# satFloat.net
KiCad netlist of a schematic drawn in Altium Designer
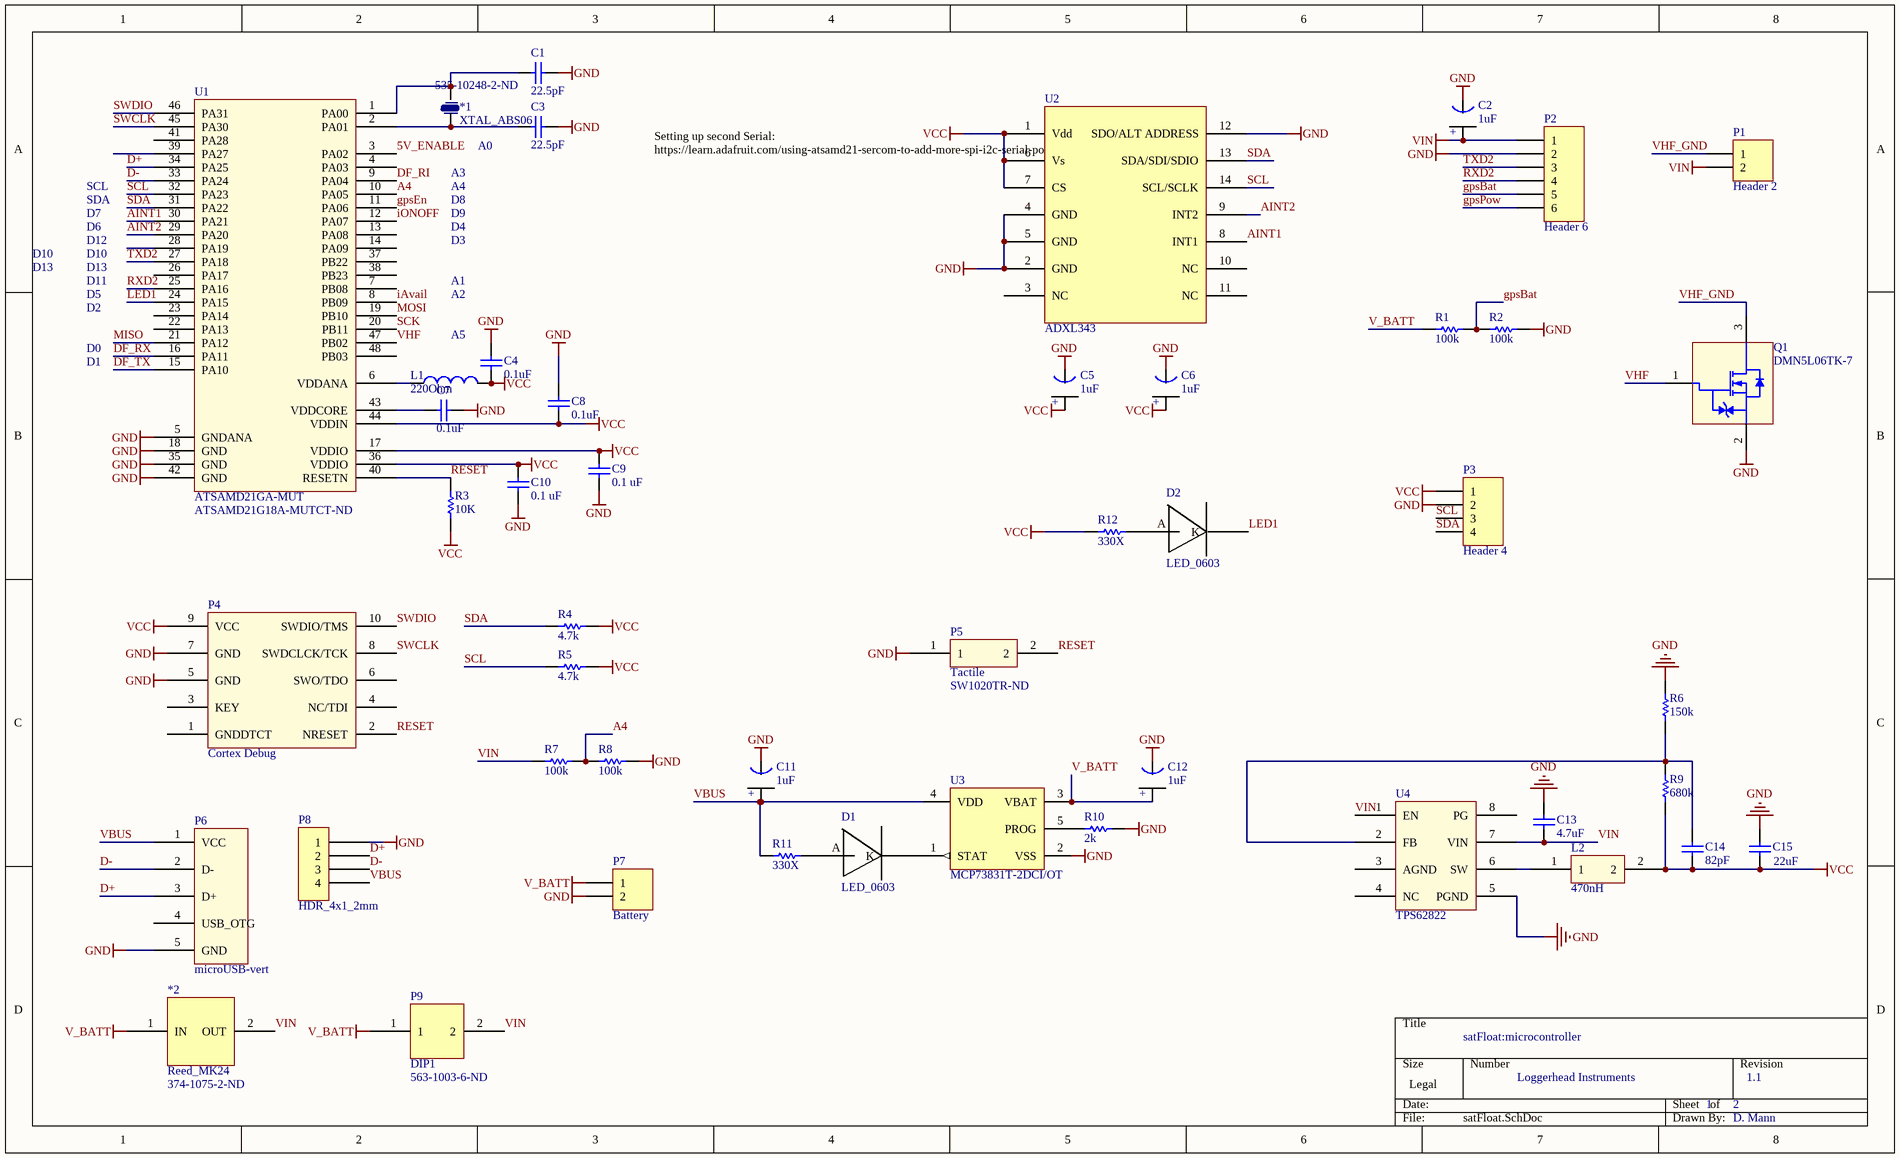
[diagram p0: satFloat.SchDoc]

(export (version "E")
  (design (tool "Eeschema 10.0.6"))
  (components
    (comp (ref "*1")
      (value "XTAL_ABS06")
      (footprint "XTAL-ABS06")
      (fields (field (name "SUPPLIER PART NUMBER 1") "535-10248-2-ND"))
      (libsource (lib "Loggerhead") (part "XTAL_ABS06"))
    )
    (comp (ref "*2")
      (value "Reed_MK24")
      (footprint "Reed MK24-B-3")
      (fields (field (name "SUPPLIER PART NUMBER 1") "374-1075-2-ND"))
      (libsource (lib "Loggerhead") (part "Reed_MK24"))
    )
    (comp (ref "C1")
      (value "22.5pF")
      (footprint "0402")
      (description "Ceramic Chip Capacitor - Standard")
      (fields (field (name "PUBLISHER") "Altium Limited"))
      (libsource (lib "KEMET Chip Capacitor") (part "C0402"))
    )
    (comp (ref "C2") (value "1uF") (footprint "Tant0805") (libsource (lib "Loggerhead") (part "Tant0805")))
    (comp (ref "C3")
      (value "22.5pF")
      (footprint "0402")
      (description "Ceramic Chip Capacitor - Standard")
      (fields (field (name "PUBLISHER") "Altium Limited"))
      (libsource (lib "KEMET Chip Capacitor") (part "C0402"))
    )
    (comp (ref "C4")
      (value "0.1uF")
      (footprint "0402")
      (description "Ceramic Chip Capacitor - Standard")
      (fields (field (name "PUBLISHER") "Altium Limited"))
      (libsource (lib "KEMET Chip Capacitor") (part "C0402"))
    )
    (comp (ref "C5") (value "1uF") (footprint "Tant0805") (libsource (lib "Loggerhead") (part "Tant0805")))
    (comp (ref "C6") (value "1uF") (footprint "Tant0805") (libsource (lib "Loggerhead") (part "Tant0805")))
    (comp (ref "C7")
      (value "0.1uF")
      (footprint "0402")
      (description "Ceramic Chip Capacitor - Standard")
      (fields (field (name "PUBLISHER") "Altium Limited"))
      (libsource (lib "KEMET Chip Capacitor") (part "C0402"))
    )
    (comp (ref "C8")
      (value "0.1uF")
      (footprint "0402")
      (description "Ceramic Chip Capacitor - Standard")
      (fields (field (name "PUBLISHER") "Altium Limited"))
      (libsource (lib "KEMET Chip Capacitor") (part "C0402"))
    )
    (comp (ref "C9")
      (value "0.1 uF")
      (footprint "0402")
      (description "Ceramic Chip Capacitor - Standard")
      (fields (field (name "PUBLISHER") "Altium Limited"))
      (libsource (lib "KEMET Chip Capacitor") (part "C0402"))
    )
    (comp (ref "C10")
      (value "0.1 uF")
      (footprint "0402")
      (description "Ceramic Chip Capacitor - Standard")
      (fields (field (name "PUBLISHER") "Altium Limited"))
      (libsource (lib "KEMET Chip Capacitor") (part "C0402"))
    )
    (comp (ref "C11") (value "1uF") (footprint "Tant0805") (libsource (lib "Loggerhead") (part "Tant0805")))
    (comp (ref "C12") (value "1uF") (footprint "Tant0805") (libsource (lib "Loggerhead") (part "Tant0805")))
    (comp (ref "C13")
      (value "4.7uF")
      (footprint "0603")
      (description "Ceramic Chip Capacitor - Standard")
      (fields (field (name "PUBLISHER") "Altium Limited"))
      (libsource (lib "KEMET Chip Capacitor") (part "C0603"))
    )
    (comp (ref "C14")
      (value "82pF")
      (footprint "0402")
      (description "Ceramic Chip Capacitor - Standard")
      (fields (field (name "PUBLISHER") "Altium Limited"))
      (libsource (lib "KEMET Chip Capacitor") (part "C0402"))
    )
    (comp (ref "C15")
      (value "22uF")
      (footprint "0603")
      (description "Ceramic Chip Capacitor - Standard")
      (fields (field (name "PUBLISHER") "Altium Limited"))
      (libsource (lib "KEMET Chip Capacitor") (part "C0603"))
    )
    (comp (ref "D1")
      (value "LED_0603")
      (footprint "Diode0603")
      (libsource (lib "Loggerhead") (part "LED_0603"))
    )
    (comp (ref "D2")
      (value "LED_0603")
      (footprint "Diode0603")
      (libsource (lib "Loggerhead") (part "LED_0603"))
    )
    (comp (ref "L1")
      (value "220Ohm")
      (footprint "0805 (M2125) Ferrite")
      (description "Ferrite 25mOhm@DC,  60 Ohm@100MHz")
      (fields
        (field (name "CREATOR AND DATE") "Design Engineer's Name")
        (field (name "FOOTPRINT VERIFIED BY") "*")
        (field (name "SCHEMATIC VERIFIED BY") "*")
        (field (name "VENDOR INFO VERIFIED BY") "*")
      )
      (libsource (lib "Flanery") (part "Ferrite 0805(M2125) 3A"))
    )
    (comp (ref "L2")
      (value "470nH")
      (footprint "Inductor_470NH")
      (libsource (lib "Loggerhead") (part "Inductor_470NH"))
    )
    (comp (ref "P1")
      (value "Header 2")
      (footprint "HDR1X2")
      (description "Header, 2-Pin")
      (fields (field (name "PUBLISHER") "Altium Limited"))
      (libsource (lib "Miscellaneous Connectors") (part "Header 2"))
    )
    (comp (ref "P2")
      (value "Header 6")
      (footprint "HDR1X6")
      (description "Header, 6-Pin")
      (fields (field (name "PUBLISHER") "Altium Limited"))
      (libsource (lib "Miscellaneous Connectors") (part "Header 6"))
    )
    (comp (ref "P3")
      (value "Header 4")
      (footprint "HDR1X4")
      (description "Header, 4-Pin")
      (fields (field (name "PUBLISHER") "Altium Limited"))
      (libsource (lib "Miscellaneous Connectors") (part "Header 4"))
    )
    (comp (ref "P4")
      (value "Cortex Debug")
      (footprint "Header_2x5_50mil")
      (libsource (lib "Loggerhead") (part "CortexDebug"))
    )
    (comp (ref "P5")
      (value "Tactile")
      (footprint "Tactile-B3U-1000")
      (fields (field (name "SUPPLIER PART NUMBER 1") "SW1020TR-ND"))
      (libsource (lib "Loggerhead") (part "Tactile_B3U-1000"))
    )
    (comp (ref "P6")
      (value "microUSB-vert")
      (footprint "MICROUSB-VERT")
      (description "Molex 105133-0011")
      (libsource (lib "Loggerhead") (part "microUSB-vert"))
    )
    (comp (ref "P7")
      (value "Battery")
      (footprint "HDR1X2")
      (description "Header, 2-Pin")
      (fields (field (name "PUBLISHER") "Altium Limited"))
      (libsource (lib "Miscellaneous Connectors") (part "Header 2"))
    )
    (comp (ref "P8")
      (value "HDR_4x1_2mm")
      (footprint "Hdr_4x1_2mm")
      (libsource (lib "Loggerhead") (part "HDR_4x1_2mm"))
    )
    (comp (ref "P9")
      (value "DIP1")
      (footprint "DIP1")
      (fields (field (name "SUPPLIER PART NUMBER 1") "563-1003-6-ND"))
      (libsource (lib "Loggerhead") (part "DIP1"))
    )
    (comp (ref "Q1")
      (value "DMN5L06TK-7")
      (footprint "SOT-523")
      (description "Ultra-low leakage Enhanced MOSFET")
      (fields
        (field (name "CREATOR AND DATE") "Will Flanery 2010-09-02")
        (field (name "FOOTPRINT VERIFIED BY") "*")
        (field (name "SCHEMATIC VERIFIED BY") "*")
        (field (name "VENDOR INFO VERIFIED BY") "*")
      )
      (libsource (lib "Flanery") (part "FET DMN5L06TK-7"))
    )
    (comp (ref "R1")
      (value "100k")
      (footprint "3-0603")
      (fields (field (name "PUBLISHER") "Altium Limited"))
      (libsource (lib "Panasonic Resistor") (part "ERJ3RK"))
    )
    (comp (ref "R2")
      (value "100k")
      (footprint "3-0603")
      (fields (field (name "PUBLISHER") "Altium Limited"))
      (libsource (lib "Panasonic Resistor") (part "ERJ3RK"))
    )
    (comp (ref "R3")
      (value "10K")
      (footprint "3-0603")
      (fields (field (name "PUBLISHER") "Altium Limited"))
      (libsource (lib "Panasonic Resistor") (part "ERJ3RK"))
    )
    (comp (ref "R4")
      (value "4.7k")
      (footprint "3-0603")
      (fields (field (name "PUBLISHER") "Altium Limited"))
      (libsource (lib "Panasonic Resistor") (part "ERJ3RK"))
    )
    (comp (ref "R5")
      (value "4.7k")
      (footprint "3-0603")
      (fields (field (name "PUBLISHER") "Altium Limited"))
      (libsource (lib "Panasonic Resistor") (part "ERJ3RK"))
    )
    (comp (ref "R6")
      (value "150k")
      (footprint "3-0603")
      (fields (field (name "PUBLISHER") "Altium Limited"))
      (libsource (lib "Panasonic Resistor") (part "ERJ3RK"))
    )
    (comp (ref "R7")
      (value "100k")
      (footprint "3-0603")
      (fields (field (name "PUBLISHER") "Altium Limited"))
      (libsource (lib "Panasonic Resistor") (part "ERJ3RK"))
    )
    (comp (ref "R8")
      (value "100k")
      (footprint "3-0603")
      (fields (field (name "PUBLISHER") "Altium Limited"))
      (libsource (lib "Panasonic Resistor") (part "ERJ3RK"))
    )
    (comp (ref "R9")
      (value "680k")
      (footprint "3-0603")
      (fields (field (name "PUBLISHER") "Altium Limited"))
      (libsource (lib "Panasonic Resistor") (part "ERJ3RK"))
    )
    (comp (ref "R10")
      (value "2k")
      (footprint "3-0603")
      (fields (field (name "PUBLISHER") "Altium Limited"))
      (libsource (lib "Panasonic Resistor") (part "ERJ3RK"))
    )
    (comp (ref "R11")
      (value "330X")
      (footprint "3-0603")
      (fields (field (name "PUBLISHER") "Altium Limited"))
      (libsource (lib "Panasonic Resistor") (part "ERJ3RK"))
    )
    (comp (ref "R12")
      (value "330X")
      (footprint "3-0603")
      (fields (field (name "PUBLISHER") "Altium Limited"))
      (libsource (lib "Panasonic Resistor") (part "ERJ3RK"))
    )
    (comp (ref "U1")
      (value "ATSAMD21GA-MUT")
      (footprint "QFN127P600-8N")
      (fields (field (name "SUPPLIER PART NUMBER 1") "ATSAMD21G18A-MUTCT-ND"))
      (libsource (lib "Loggerhead") (part "ATSAMD21G18"))
    )
    (comp (ref "U2") (value "ADXL343") (footprint "ADXL345") (libsource (lib "Loggerhead") (part "ADXL345")))
    (comp (ref "U3")
      (value "MCP73831T-2DCI/OT")
      (footprint "SOT-23-OT5_N")
      (libsource (lib "Microchip Power Management Battery Management") (part "MCP73831T-2DCI/OT"))
    )
    (comp (ref "U4")
      (value "TPS62822")
      (footprint "TPS62822_SOP8")
      (description "Step-down converter")
      (libsource (lib "Loggerhead") (part "TPS62822"))
    )
  )
  (nets
    (net (code "1") (name "/5V_ENABLE") (class "Default")
      (node (ref "U1") (pin "3") (pinfunction "PA02_3") (pintype "passive"))
    )
    (net (code "2") (name "/A4") (class "Default")
      (node (ref "R7") (pin "1") (pinfunction "1_1") (pintype "passive"))
      (node (ref "R8") (pin "2") (pinfunction "2_2") (pintype "passive"))
      (node (ref "U1") (pin "10") (pinfunction "PA05_10") (pintype "passive"))
    )
    (net (code "3") (name "/AINT1") (class "Default")
      (node (ref "U1") (pin "30") (pinfunction "PA21_30") (pintype "passive"))
      (node (ref "U2") (pin "8") (pinfunction "INT1_8") (pintype "passive"))
    )
    (net (code "4") (name "/AINT2") (class "Default")
      (node (ref "U1") (pin "29") (pinfunction "PA20_29") (pintype "passive"))
      (node (ref "U2") (pin "9") (pinfunction "INT2_9") (pintype "passive"))
    )
    (net (code "5") (name "/D+") (class "Default")
      (node (ref "P6") (pin "3") (pinfunction "D+_3") (pintype "passive"))
      (node (ref "P8") (pin "2") (pinfunction "2_2") (pintype "passive"))
      (node (ref "U1") (pin "34") (pinfunction "PA25_34") (pintype "passive"))
    )
    (net (code "6") (name "/D-") (class "Default")
      (node (ref "P6") (pin "2") (pinfunction "D-_2") (pintype "passive"))
      (node (ref "P8") (pin "3") (pinfunction "3_3") (pintype "passive"))
      (node (ref "U1") (pin "33") (pinfunction "PA24_33") (pintype "passive"))
    )
    (net (code "7") (name "/DF_RI") (class "Default")
      (node (ref "U1") (pin "9") (pinfunction "PA04_9") (pintype "passive"))
    )
    (net (code "8") (name "/DF_RX") (class "Default")
      (node (ref "U1") (pin "16") (pinfunction "PA11_16") (pintype "passive"))
    )
    (net (code "9") (name "/DF_TX") (class "Default")
      (node (ref "U1") (pin "15") (pinfunction "PA10_15") (pintype "passive"))
    )
    (net (code "10") (name "/LED1") (class "Default")
      (node (ref "D2") (pin "K") (pinfunction "K_K") (pintype "passive"))
      (node (ref "U1") (pin "24") (pinfunction "PA15_24") (pintype "passive"))
    )
    (net (code "11") (name "/MISO") (class "Default")
      (node (ref "U1") (pin "21") (pinfunction "PA12_21") (pintype "passive"))
    )
    (net (code "12") (name "/MOSI") (class "Default")
      (node (ref "U1") (pin "19") (pinfunction "PB10_19") (pintype "passive"))
    )
    (net (code "13") (name "/RESET") (class "Default")
      (node (ref "P4") (pin "2") (pinfunction "NRESET_2") (pintype "passive"))
      (node (ref "P5") (pin "2") (pinfunction "2_2") (pintype "passive"))
      (node (ref "R3") (pin "2") (pinfunction "2_2") (pintype "passive"))
      (node (ref "U1") (pin "40") (pinfunction "RESETN_40") (pintype "passive"))
    )
    (net (code "14") (name "/RXD2") (class "Default")
      (node (ref "P2") (pin "4") (pinfunction "4_4") (pintype "passive"))
      (node (ref "U1") (pin "25") (pinfunction "PA16_25") (pintype "passive"))
    )
    (net (code "15") (name "/SCK") (class "Default")
      (node (ref "U1") (pin "20") (pinfunction "PB11_20") (pintype "passive"))
    )
    (net (code "16") (name "/SCL") (class "Default")
      (node (ref "P3") (pin "3") (pinfunction "3_3") (pintype "passive"))
      (node (ref "R5") (pin "1") (pinfunction "1_1") (pintype "passive"))
      (node (ref "U1") (pin "32") (pinfunction "PA23_32") (pintype "passive"))
      (node (ref "U2") (pin "14") (pinfunction "SCL/SCLK_14") (pintype "passive"))
    )
    (net (code "17") (name "/SDA") (class "Default")
      (node (ref "P3") (pin "4") (pinfunction "4_4") (pintype "passive"))
      (node (ref "R4") (pin "2") (pinfunction "2_2") (pintype "passive"))
      (node (ref "U1") (pin "31") (pinfunction "PA22_31") (pintype "passive"))
      (node (ref "U2") (pin "13") (pinfunction "SDA/SDI/SDIO_13") (pintype "passive"))
    )
    (net (code "18") (name "/SWCLK") (class "Default")
      (node (ref "P4") (pin "8") (pinfunction "SWDCLCK/TCK_8") (pintype "passive"))
      (node (ref "U1") (pin "45") (pinfunction "PA30_45") (pintype "passive"))
    )
    (net (code "19") (name "/SWDIO") (class "Default")
      (node (ref "P4") (pin "10") (pinfunction "SWDIO/TMS_10") (pintype "passive"))
      (node (ref "U1") (pin "46") (pinfunction "PA31_46") (pintype "passive"))
    )
    (net (code "20") (name "/TXD2") (class "Default")
      (node (ref "P2") (pin "3") (pinfunction "3_3") (pintype "passive"))
      (node (ref "U1") (pin "27") (pinfunction "PA18_27") (pintype "passive"))
    )
    (net (code "21") (name "/VBUS") (class "Default")
      (node (ref "C11") (pin "2") (pinfunction "+_2") (pintype "passive"))
      (node (ref "P6") (pin "1") (pinfunction "VCC_1") (pintype "passive"))
      (node (ref "P8") (pin "4") (pinfunction "4_4") (pintype "passive"))
      (node (ref "R11") (pin "1") (pinfunction "1_1") (pintype "passive"))
      (node (ref "U3") (pin "4") (pinfunction "VDD_4") (pintype "power_in"))
    )
    (net (code "22") (name "/VHF") (class "Default")
      (node (ref "Q1") (pin "1") (pinfunction "G_1") (pintype "passive"))
      (node (ref "U1") (pin "47") (pinfunction "PB02_47") (pintype "passive"))
    )
    (net (code "23") (name "/VHF_GND") (class "Default")
      (node (ref "P1") (pin "1") (pinfunction "1_1") (pintype "passive"))
      (node (ref "Q1") (pin "3") (pinfunction "D_3") (pintype "passive"))
    )
    (net (code "24") (name "/gpsBat") (class "Default")
      (node (ref "P2") (pin "5") (pinfunction "5_5") (pintype "passive"))
      (node (ref "R1") (pin "1") (pinfunction "1_1") (pintype "passive"))
      (node (ref "R2") (pin "2") (pinfunction "2_2") (pintype "passive"))
    )
    (net (code "25") (name "/gpsEn") (class "Default")
      (node (ref "U1") (pin "11") (pinfunction "PA06_11") (pintype "passive"))
    )
    (net (code "26") (name "/gpsPow") (class "Default")
      (node (ref "P2") (pin "6") (pinfunction "6_6") (pintype "passive"))
    )
    (net (code "27") (name "/iAvail") (class "Default")
      (node (ref "U1") (pin "8") (pinfunction "PB09_8") (pintype "passive"))
    )
    (net (code "28") (name "/iONOFF") (class "Default")
      (node (ref "U1") (pin "12") (pinfunction "PA07_12") (pintype "passive"))
    )
    (net (code "29") (name "GND") (class "Default")
      (node (ref "C1") (pin "1") (pinfunction "1_1") (pintype "passive"))
      (node (ref "C10") (pin "2") (pinfunction "2_2") (pintype "passive"))
      (node (ref "C11") (pin "1") (pinfunction "GND_1") (pintype "passive"))
      (node (ref "C12") (pin "1") (pinfunction "GND_1") (pintype "passive"))
      (node (ref "C13") (pin "1") (pinfunction "1_1") (pintype "passive"))
      (node (ref "C15") (pin "1") (pinfunction "1_1") (pintype "passive"))
      (node (ref "C2") (pin "1") (pinfunction "GND_1") (pintype "passive"))
      (node (ref "C3") (pin "1") (pinfunction "1_1") (pintype "passive"))
      (node (ref "C4") (pin "2") (pinfunction "2_2") (pintype "passive"))
      (node (ref "C5") (pin "1") (pinfunction "GND_1") (pintype "passive"))
      (node (ref "C6") (pin "1") (pinfunction "GND_1") (pintype "passive"))
      (node (ref "C7") (pin "2") (pinfunction "2_2") (pintype "passive"))
      (node (ref "C8") (pin "2") (pinfunction "2_2") (pintype "passive"))
      (node (ref "C9") (pin "2") (pinfunction "2_2") (pintype "passive"))
      (node (ref "P2") (pin "2") (pinfunction "2_2") (pintype "passive"))
      (node (ref "P3") (pin "2") (pinfunction "2_2") (pintype "passive"))
      (node (ref "P4") (pin "5") (pinfunction "GND_5") (pintype "passive"))
      (node (ref "P4") (pin "7") (pinfunction "GND_7") (pintype "passive"))
      (node (ref "P5") (pin "1") (pinfunction "1_1") (pintype "passive"))
      (node (ref "P6") (pin "5") (pinfunction "GND_5") (pintype "passive"))
      (node (ref "P7") (pin "2") (pinfunction "2_2") (pintype "passive"))
      (node (ref "P8") (pin "1") (pinfunction "1_1") (pintype "passive"))
      (node (ref "Q1") (pin "2") (pinfunction "S_2") (pintype "passive"))
      (node (ref "R10") (pin "1") (pinfunction "1_1") (pintype "passive"))
      (node (ref "R2") (pin "1") (pinfunction "1_1") (pintype "passive"))
      (node (ref "R6") (pin "2") (pinfunction "2_2") (pintype "passive"))
      (node (ref "R8") (pin "1") (pinfunction "1_1") (pintype "passive"))
      (node (ref "U1") (pin "18") (pinfunction "GND_18") (pintype "passive"))
      (node (ref "U1") (pin "35") (pinfunction "GND_35") (pintype "passive"))
      (node (ref "U1") (pin "42") (pinfunction "GND_42") (pintype "passive"))
      (node (ref "U1") (pin "5") (pinfunction "GNDANA_5") (pintype "passive"))
      (node (ref "U2") (pin "12") (pinfunction "SDO/ALT_ADDRESS_12") (pintype "passive"))
      (node (ref "U2") (pin "2") (pinfunction "GND_2") (pintype "passive"))
      (node (ref "U2") (pin "4") (pinfunction "GND_4") (pintype "passive"))
      (node (ref "U2") (pin "5") (pinfunction "GND_5") (pintype "passive"))
      (node (ref "U3") (pin "2") (pinfunction "VSS_2") (pintype "power_in"))
      (node (ref "U4") (pin "5") (pinfunction "PGND_5") (pintype "passive"))
    )
    (net (code "30") (name "Net-(D1-PadA)") (class "Default")
      (node (ref "D1") (pin "A") (pinfunction "A_A") (pintype "passive"))
      (node (ref "R11") (pin "2") (pinfunction "2_2") (pintype "passive"))
    )
    (net (code "31") (name "Net-(D2-PadA)") (class "Default")
      (node (ref "D2") (pin "A") (pinfunction "A_A") (pintype "passive"))
      (node (ref "R12") (pin "2") (pinfunction "2_2") (pintype "passive"))
    )
    (net (code "32") (name "Net-(U1-PA00)") (class "Default")
      (node (ref "*1") (pin "2") (pinfunction "2_2") (pintype "passive"))
      (node (ref "C1") (pin "2") (pinfunction "2_2") (pintype "passive"))
      (node (ref "U1") (pin "1") (pinfunction "PA00_1") (pintype "passive"))
    )
    (net (code "33") (name "Net-(U1-PA01)") (class "Default")
      (node (ref "*1") (pin "1") (pinfunction "1_1") (pintype "passive"))
      (node (ref "C3") (pin "2") (pinfunction "2_2") (pintype "passive"))
      (node (ref "U1") (pin "2") (pinfunction "PA01_2") (pintype "passive"))
    )
    (net (code "34") (name "Net-(U1-VDDANA)") (class "Default")
      (node (ref "L1") (pin "1") (pinfunction "1_1") (pintype "passive"))
      (node (ref "U1") (pin "6") (pinfunction "VDDANA_6") (pintype "passive"))
    )
    (net (code "35") (name "Net-(U1-VDDCORE)") (class "Default")
      (node (ref "C7") (pin "1") (pinfunction "1_1") (pintype "passive"))
      (node (ref "U1") (pin "43") (pinfunction "VDDCORE_43") (pintype "passive"))
    )
    (net (code "36") (name "Net-(U3-PROG)") (class "Default")
      (node (ref "R10") (pin "2") (pinfunction "2_2") (pintype "passive"))
      (node (ref "U3") (pin "5") (pinfunction "PROG_5") (pintype "passive"))
    )
    (net (code "37") (name "Net-(U3-STAT)") (class "Default")
      (node (ref "D1") (pin "K") (pinfunction "K_K") (pintype "passive"))
      (node (ref "U3") (pin "1") (pinfunction "STAT_1") (pintype "output"))
    )
    (net (code "38") (name "Net-(U4-FB)") (class "Default")
      (node (ref "C14") (pin "2") (pinfunction "2_2") (pintype "passive"))
      (node (ref "R6") (pin "1") (pinfunction "1_1") (pintype "passive"))
      (node (ref "R9") (pin "2") (pinfunction "2_2") (pintype "passive"))
      (node (ref "U4") (pin "2") (pinfunction "FB_2") (pintype "passive"))
    )
    (net (code "39") (name "Net-(U4-SW)") (class "Default")
      (node (ref "L2") (pin "1") (pinfunction "1_1") (pintype "passive"))
      (node (ref "U4") (pin "6") (pinfunction "SW_6") (pintype "passive"))
    )
    (net (code "40") (name "VCC") (class "Default")
      (node (ref "C10") (pin "1") (pinfunction "1_1") (pintype "passive"))
      (node (ref "C14") (pin "1") (pinfunction "1_1") (pintype "passive"))
      (node (ref "C15") (pin "2") (pinfunction "2_2") (pintype "passive"))
      (node (ref "C4") (pin "1") (pinfunction "1_1") (pintype "passive"))
      (node (ref "C5") (pin "2") (pinfunction "+_2") (pintype "passive"))
      (node (ref "C6") (pin "2") (pinfunction "+_2") (pintype "passive"))
      (node (ref "C8") (pin "1") (pinfunction "1_1") (pintype "passive"))
      (node (ref "C9") (pin "1") (pinfunction "1_1") (pintype "passive"))
      (node (ref "L1") (pin "2") (pinfunction "2_2") (pintype "passive"))
      (node (ref "L2") (pin "2") (pinfunction "2_2") (pintype "passive"))
      (node (ref "P3") (pin "1") (pinfunction "1_1") (pintype "passive"))
      (node (ref "P4") (pin "9") (pinfunction "VCC_9") (pintype "passive"))
      (node (ref "R12") (pin "1") (pinfunction "1_1") (pintype "passive"))
      (node (ref "R3") (pin "1") (pinfunction "1_1") (pintype "passive"))
      (node (ref "R4") (pin "1") (pinfunction "1_1") (pintype "passive"))
      (node (ref "R5") (pin "2") (pinfunction "2_2") (pintype "passive"))
      (node (ref "R9") (pin "1") (pinfunction "1_1") (pintype "passive"))
      (node (ref "U1") (pin "17") (pinfunction "VDDIO_17") (pintype "passive"))
      (node (ref "U1") (pin "36") (pinfunction "VDDIO_36") (pintype "passive"))
      (node (ref "U1") (pin "44") (pinfunction "VDDIN_44") (pintype "passive"))
      (node (ref "U2") (pin "1") (pinfunction "Vdd_1") (pintype "power_in"))
      (node (ref "U2") (pin "6") (pinfunction "Vs_6") (pintype "passive"))
      (node (ref "U2") (pin "7") (pinfunction "CS_7") (pintype "passive"))
    )
    (net (code "41") (name "VIN") (class "Default")
      (node (ref "*2") (pin "2") (pinfunction "OUT_2") (pintype "passive"))
      (node (ref "C13") (pin "2") (pinfunction "2_2") (pintype "passive"))
      (node (ref "C2") (pin "2") (pinfunction "+_2") (pintype "passive"))
      (node (ref "P1") (pin "2") (pinfunction "2_2") (pintype "passive"))
      (node (ref "P2") (pin "1") (pinfunction "1_1") (pintype "passive"))
      (node (ref "P9") (pin "2") (pinfunction "2_2") (pintype "passive"))
      (node (ref "R7") (pin "2") (pinfunction "2_2") (pintype "passive"))
      (node (ref "U4") (pin "1") (pinfunction "EN_1") (pintype "passive"))
      (node (ref "U4") (pin "7") (pinfunction "VIN_7") (pintype "passive"))
    )
    (net (code "42") (name "V_BATT") (class "Default")
      (node (ref "*2") (pin "1") (pinfunction "IN_1") (pintype "passive"))
      (node (ref "C12") (pin "2") (pinfunction "+_2") (pintype "passive"))
      (node (ref "P7") (pin "1") (pinfunction "1_1") (pintype "passive"))
      (node (ref "P9") (pin "1") (pinfunction "1_1") (pintype "passive"))
      (node (ref "R1") (pin "2") (pinfunction "2_2") (pintype "passive"))
      (node (ref "U3") (pin "3") (pinfunction "VBAT_3") (pintype "power_in"))
    )
    (net (code "43") (name "unconnected-(P4-GNDDTCT-Pad1)") (class "Default")
      (node (ref "P4") (pin "1") (pinfunction "GNDDTCT_1") (pintype "passive"))
    )
    (net (code "44") (name "unconnected-(P4-KEY-Pad3)") (class "Default")
      (node (ref "P4") (pin "3") (pinfunction "KEY_3") (pintype "passive"))
    )
    (net (code "45") (name "unconnected-(P4-NC{slash}TDI-Pad4)") (class "Default")
      (node (ref "P4") (pin "4") (pinfunction "NC/TDI_4") (pintype "passive"))
    )
    (net (code "46") (name "unconnected-(P4-SWO{slash}TDO-Pad6)") (class "Default")
      (node (ref "P4") (pin "6") (pinfunction "SWO/TDO_6") (pintype "passive"))
    )
    (net (code "47") (name "unconnected-(P6-USB_OTG-Pad4)") (class "Default")
      (node (ref "P6") (pin "4") (pinfunction "USB_OTG_4") (pintype "passive"))
    )
    (net (code "48") (name "unconnected-(U1-PA03-Pad4)") (class "Default")
      (node (ref "U1") (pin "4") (pinfunction "PA03_4") (pintype "passive"))
    )
    (net (code "49") (name "unconnected-(U1-PA08-Pad13)") (class "Default")
      (node (ref "U1") (pin "13") (pinfunction "PA08_13") (pintype "passive"))
    )
    (net (code "50") (name "unconnected-(U1-PA09-Pad14)") (class "Default")
      (node (ref "U1") (pin "14") (pinfunction "PA09_14") (pintype "passive"))
    )
    (net (code "51") (name "unconnected-(U1-PA13-Pad22)") (class "Default")
      (node (ref "U1") (pin "22") (pinfunction "PA13_22") (pintype "passive"))
    )
    (net (code "52") (name "unconnected-(U1-PA14-Pad23)") (class "Default")
      (node (ref "U1") (pin "23") (pinfunction "PA14_23") (pintype "passive"))
    )
    (net (code "53") (name "unconnected-(U1-PA17-Pad26)") (class "Default")
      (node (ref "U1") (pin "26") (pinfunction "PA17_26") (pintype "passive"))
    )
    (net (code "54") (name "unconnected-(U1-PA19-Pad28)") (class "Default")
      (node (ref "U1") (pin "28") (pinfunction "PA19_28") (pintype "passive"))
    )
    (net (code "55") (name "unconnected-(U1-PA27-Pad39)") (class "Default")
      (node (ref "U1") (pin "39") (pinfunction "PA27_39") (pintype "passive"))
    )
    (net (code "56") (name "unconnected-(U1-PA28-Pad41)") (class "Default")
      (node (ref "U1") (pin "41") (pinfunction "PA28_41") (pintype "passive"))
    )
    (net (code "57") (name "unconnected-(U1-PB03-Pad48)") (class "Default")
      (node (ref "U1") (pin "48") (pinfunction "PB03_48") (pintype "passive"))
    )
    (net (code "58") (name "unconnected-(U1-PB08-Pad7)") (class "Default")
      (node (ref "U1") (pin "7") (pinfunction "PB08_7") (pintype "passive"))
    )
    (net (code "59") (name "unconnected-(U1-PB22-Pad37)") (class "Default")
      (node (ref "U1") (pin "37") (pinfunction "PB22_37") (pintype "passive"))
    )
    (net (code "60") (name "unconnected-(U1-PB23-Pad38)") (class "Default")
      (node (ref "U1") (pin "38") (pinfunction "PB23_38") (pintype "passive"))
    )
    (net (code "61") (name "unconnected-(U2-NC-Pad3)") (class "Default")
      (node (ref "U2") (pin "3") (pinfunction "NC_3") (pintype "passive"))
    )
    (net (code "62") (name "unconnected-(U2-NC-Pad10)") (class "Default")
      (node (ref "U2") (pin "10") (pinfunction "NC_10") (pintype "passive"))
    )
    (net (code "63") (name "unconnected-(U2-NC-Pad11)") (class "Default")
      (node (ref "U2") (pin "11") (pinfunction "NC_11") (pintype "passive"))
    )
    (net (code "64") (name "unconnected-(U4-AGND-Pad3)") (class "Default")
      (node (ref "U4") (pin "3") (pinfunction "AGND_3") (pintype "passive"))
    )
    (net (code "65") (name "unconnected-(U4-NC-Pad4)") (class "Default")
      (node (ref "U4") (pin "4") (pinfunction "NC_4") (pintype "passive"))
    )
    (net (code "66") (name "unconnected-(U4-PG-Pad8)") (class "Default")
      (node (ref "U4") (pin "8") (pinfunction "PG_8") (pintype "passive"))
    )
  )
)
